# 4pwm.net
KiCad netlist of a schematic drawn in EAGLE
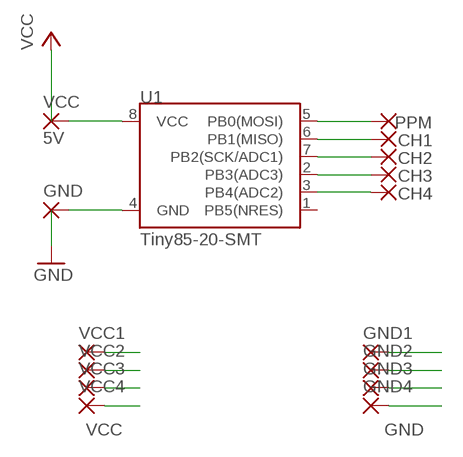
[diagram p0: schematic, sheet 1]

(export (version "E")
  (design (tool "Eeschema 10.0.6"))
  (components
    (comp (ref "CH1")
      (value "SMD2")
      (footprint "eagle-import:SMD1,27-2,54")
      (libsource (lib "eagle-import") (part "SMD2"))
    )
    (comp (ref "CH2")
      (value "SMD2")
      (footprint "eagle-import:SMD1,27-2,54")
      (libsource (lib "eagle-import") (part "SMD2"))
    )
    (comp (ref "CH3")
      (value "SMD2")
      (footprint "eagle-import:SMD1,27-2,54")
      (libsource (lib "eagle-import") (part "SMD2"))
    )
    (comp (ref "CH4")
      (value "SMD2")
      (footprint "eagle-import:SMD1,27-2,54")
      (libsource (lib "eagle-import") (part "SMD2"))
    )
    (comp (ref "GND")
      (value "SMD2")
      (footprint "eagle-import:SMD1,27-2,54")
      (libsource (lib "eagle-import") (part "SMD2"))
    )
    (comp (ref "GND1")
      (value "SMD2")
      (footprint "eagle-import:SMD1,27-2,54")
      (libsource (lib "eagle-import") (part "SMD2"))
    )
    (comp (ref "GND2")
      (value "SMD2")
      (footprint "eagle-import:SMD1,27-2,54")
      (libsource (lib "eagle-import") (part "SMD2"))
    )
    (comp (ref "GND3")
      (value "SMD2")
      (footprint "eagle-import:SMD1,27-2,54")
      (libsource (lib "eagle-import") (part "SMD2"))
    )
    (comp (ref "GND4")
      (value "SMD2")
      (footprint "eagle-import:SMD1,27-2,54")
      (libsource (lib "eagle-import") (part "SMD2"))
    )
    (comp (ref "PPM")
      (value "SMD2")
      (footprint "eagle-import:SMD1,27-2,54")
      (libsource (lib "eagle-import") (part "SMD2"))
    )
    (comp (ref "U1")
      (value "Tiny85-20-SMT")
      (footprint "eagle-import:SO08-EIAJ")
      (libsource (lib "eagle-import") (part "ATTINY45TINY85-20-SMT"))
    )
    (comp (ref "VCC")
      (value "5V")
      (footprint "eagle-import:SMD1,27-2,54")
      (libsource (lib "eagle-import") (part "SMD2"))
    )
    (comp (ref "VCC1")
      (value "SMD2")
      (footprint "eagle-import:SMD1,27-2,54")
      (libsource (lib "eagle-import") (part "SMD2"))
    )
    (comp (ref "VCC2")
      (value "SMD2")
      (footprint "eagle-import:SMD1,27-2,54")
      (libsource (lib "eagle-import") (part "SMD2"))
    )
    (comp (ref "VCC3")
      (value "SMD2")
      (footprint "eagle-import:SMD1,27-2,54")
      (libsource (lib "eagle-import") (part "SMD2"))
    )
    (comp (ref "VCC4")
      (value "SMD2")
      (footprint "eagle-import:SMD1,27-2,54")
      (libsource (lib "eagle-import") (part "SMD2"))
    )
  )
  (nets
    (net (code "1") (name "GND") (class "Default")
      (node (ref "GND") (pin "1") (pinfunction "P_1") (pintype "passive"))
      (node (ref "GND1") (pin "1") (pinfunction "P_1") (pintype "passive"))
      (node (ref "GND2") (pin "1") (pinfunction "P_1") (pintype "passive"))
      (node (ref "GND3") (pin "1") (pinfunction "P_1") (pintype "passive"))
      (node (ref "GND4") (pin "1") (pinfunction "P_1") (pintype "passive"))
      (node (ref "U1") (pin "4") (pinfunction "GND_4") (pintype "bidirectional"))
    )
    (net (code "2") (name "Net-(CH1-P)") (class "Default")
      (node (ref "CH1") (pin "1") (pinfunction "P_1") (pintype "passive"))
      (node (ref "U1") (pin "6") (pinfunction "PB1(MISO)_6") (pintype "bidirectional"))
    )
    (net (code "3") (name "Net-(CH2-P)") (class "Default")
      (node (ref "CH2") (pin "1") (pinfunction "P_1") (pintype "passive"))
      (node (ref "U1") (pin "7") (pinfunction "PB2(SCK/ADC1)_7") (pintype "bidirectional"))
    )
    (net (code "4") (name "Net-(CH3-P)") (class "Default")
      (node (ref "CH3") (pin "1") (pinfunction "P_1") (pintype "passive"))
      (node (ref "U1") (pin "2") (pinfunction "PB3(ADC3)_2") (pintype "bidirectional"))
    )
    (net (code "5") (name "Net-(CH4-P)") (class "Default")
      (node (ref "CH4") (pin "1") (pinfunction "P_1") (pintype "passive"))
      (node (ref "U1") (pin "3") (pinfunction "PB4(ADC2)_3") (pintype "bidirectional"))
    )
    (net (code "6") (name "Net-(PPM-P)") (class "Default")
      (node (ref "PPM") (pin "1") (pinfunction "P_1") (pintype "passive"))
      (node (ref "U1") (pin "5") (pinfunction "PB0(MOSI)_5") (pintype "bidirectional"))
    )
    (net (code "7") (name "VCC") (class "Default")
      (node (ref "U1") (pin "8") (pinfunction "VCC_8") (pintype "bidirectional"))
      (node (ref "VCC") (pin "1") (pinfunction "P_1") (pintype "passive"))
      (node (ref "VCC1") (pin "1") (pinfunction "P_1") (pintype "passive"))
      (node (ref "VCC2") (pin "1") (pinfunction "P_1") (pintype "passive"))
      (node (ref "VCC3") (pin "1") (pinfunction "P_1") (pintype "passive"))
      (node (ref "VCC4") (pin "1") (pinfunction "P_1") (pintype "passive"))
    )
    (net (code "8") (name "unconnected-(U1-PB5(NRES)-Pad1)") (class "Default")
      (node (ref "U1") (pin "1") (pinfunction "PB5(NRES)_1") (pintype "bidirectional"))
    )
  )
)
